# PCB_0009.net
KiCad netlist of a schematic drawn in EAGLE
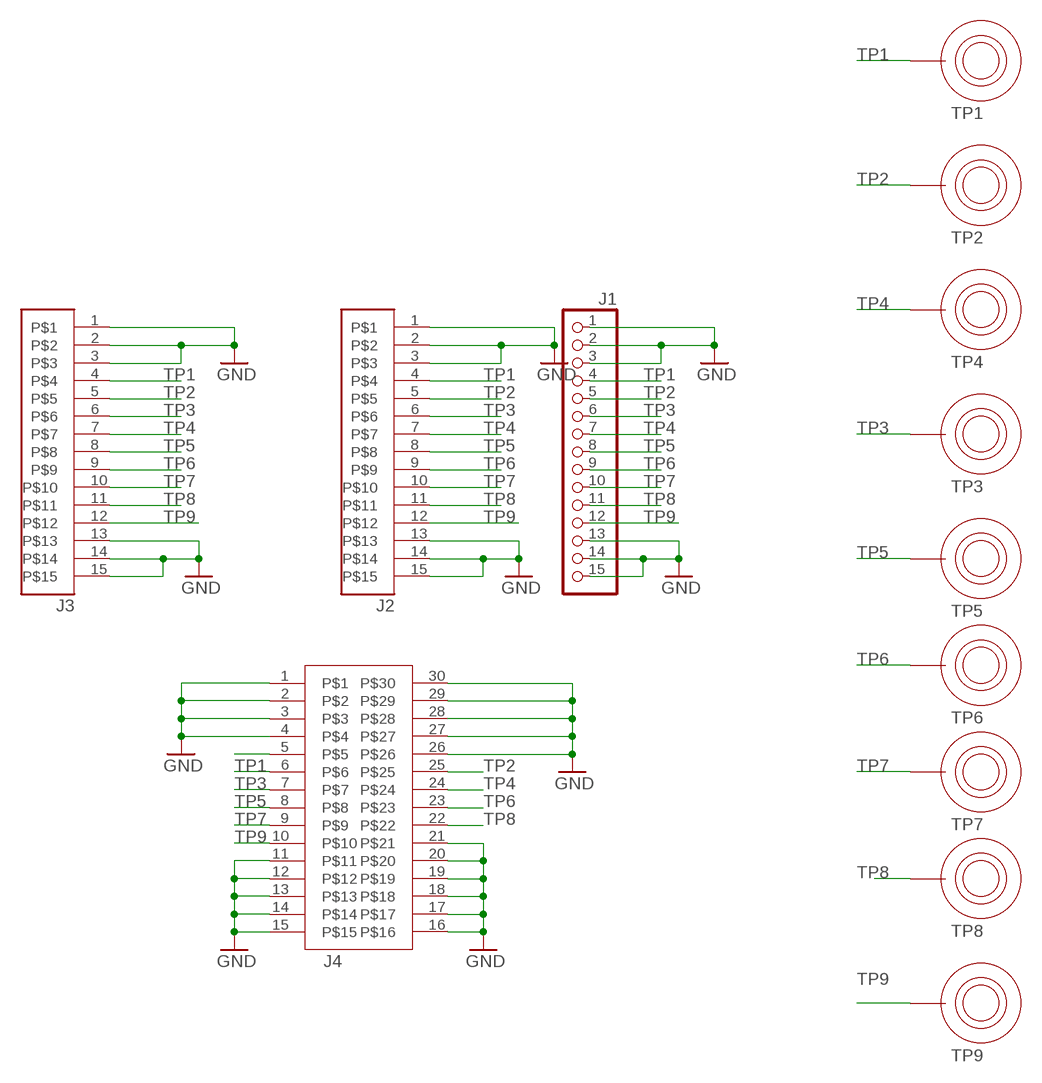
[diagram p0: schematic, sheet 1]

(export (version "E")
  (design (tool "Eeschema 10.0.6"))
  (components
    (comp (ref "J1")
      (value "PINHD-1X15")
      (footprint "eagle-import:1X15")
      (libsource (lib "eagle-import") (part "PINHD-1X15"))
    )
    (comp (ref "J2")
      (value "HEADER_15X1RA_SMT_HACK")
      (footprint "eagle-import:HEADER_1X15_RA_SMT_HACK")
      (libsource (lib "eagle-import") (part "HEADER_15X1RA_SMT_HACK"))
    )
    (comp (ref "J3")
      (value "HEADER_15X1SMT")
      (footprint "eagle-import:HDRV_SMD_15S736P254_1X15_3860X508X965")
      (libsource (lib "eagle-import") (part "HEADER_15X1SMT"))
    )
    (comp (ref "J4")
      (value "HEADER_15X2SMT")
      (footprint "eagle-import:HDRV_SMD_30S736P254_2X15_3860X508X965")
      (libsource (lib "eagle-import") (part "HEADER_15X2SMT"))
    )
    (comp (ref "TP1")
      (value "TOUCHPADROUND15MM")
      (footprint "eagle-import:TOUCHPAD_ROUND_15MM")
      (libsource (lib "eagle-import") (part "TOUCHPADROUND15MM"))
    )
    (comp (ref "TP2")
      (value "TOUCHPADROUND15MM")
      (footprint "eagle-import:TOUCHPAD_ROUND_15MM")
      (libsource (lib "eagle-import") (part "TOUCHPADROUND15MM"))
    )
    (comp (ref "TP3")
      (value "TOUCHPADROUND15MM")
      (footprint "eagle-import:TOUCHPAD_ROUND_15MM")
      (libsource (lib "eagle-import") (part "TOUCHPADROUND15MM"))
    )
    (comp (ref "TP4")
      (value "TOUCHPADROUND15MM")
      (footprint "eagle-import:TOUCHPAD_ROUND_15MM")
      (libsource (lib "eagle-import") (part "TOUCHPADROUND15MM"))
    )
    (comp (ref "TP5")
      (value "TOUCHPADROUND15MM")
      (footprint "eagle-import:TOUCHPAD_ROUND_15MM")
      (libsource (lib "eagle-import") (part "TOUCHPADROUND15MM"))
    )
    (comp (ref "TP6")
      (value "TOUCHPADROUND15MM")
      (footprint "eagle-import:TOUCHPAD_ROUND_15MM")
      (libsource (lib "eagle-import") (part "TOUCHPADROUND15MM"))
    )
    (comp (ref "TP7")
      (value "TOUCHPADROUND15MM")
      (footprint "eagle-import:TOUCHPAD_ROUND_15MM")
      (libsource (lib "eagle-import") (part "TOUCHPADROUND15MM"))
    )
    (comp (ref "TP8")
      (value "TOUCHPADROUND15MM")
      (footprint "eagle-import:TOUCHPAD_ROUND_15MM")
      (libsource (lib "eagle-import") (part "TOUCHPADROUND15MM"))
    )
    (comp (ref "TP9")
      (value "TOUCHPADROUND15MM")
      (footprint "eagle-import:TOUCHPAD_ROUND_15MM")
      (libsource (lib "eagle-import") (part "TOUCHPADROUND15MM"))
    )
  )
  (nets
    (net (code "1") (name "/TP1") (class "Default")
      (node (ref "J1") (pin "4") (pinfunction "4_4") (pintype "passive"))
      (node (ref "J2") (pin "4") (pinfunction "P$4_4") (pintype "bidirectional"))
      (node (ref "J3") (pin "4") (pinfunction "P$4_4") (pintype "bidirectional"))
      (node (ref "J4") (pin "6") (pinfunction "P$6_6") (pintype "bidirectional"))
      (node (ref "TP1") (pin "P$1") (pinfunction "P$1_P$1") (pintype "bidirectional"))
    )
    (net (code "2") (name "/TP2") (class "Default")
      (node (ref "J1") (pin "5") (pinfunction "5_5") (pintype "passive"))
      (node (ref "J2") (pin "5") (pinfunction "P$5_5") (pintype "bidirectional"))
      (node (ref "J3") (pin "5") (pinfunction "P$5_5") (pintype "bidirectional"))
      (node (ref "J4") (pin "25") (pinfunction "P$25_25") (pintype "bidirectional"))
      (node (ref "TP2") (pin "P$1") (pinfunction "P$1_P$1") (pintype "bidirectional"))
    )
    (net (code "3") (name "/TP3") (class "Default")
      (node (ref "J1") (pin "6") (pinfunction "6_6") (pintype "passive"))
      (node (ref "J2") (pin "6") (pinfunction "P$6_6") (pintype "bidirectional"))
      (node (ref "J3") (pin "6") (pinfunction "P$6_6") (pintype "bidirectional"))
      (node (ref "J4") (pin "7") (pinfunction "P$7_7") (pintype "bidirectional"))
      (node (ref "TP3") (pin "P$1") (pinfunction "P$1_P$1") (pintype "bidirectional"))
    )
    (net (code "4") (name "/TP4") (class "Default")
      (node (ref "J1") (pin "7") (pinfunction "7_7") (pintype "passive"))
      (node (ref "J2") (pin "7") (pinfunction "P$7_7") (pintype "bidirectional"))
      (node (ref "J3") (pin "7") (pinfunction "P$7_7") (pintype "bidirectional"))
      (node (ref "J4") (pin "24") (pinfunction "P$24_24") (pintype "bidirectional"))
      (node (ref "TP4") (pin "P$1") (pinfunction "P$1_P$1") (pintype "bidirectional"))
    )
    (net (code "5") (name "/TP5") (class "Default")
      (node (ref "J1") (pin "8") (pinfunction "8_8") (pintype "passive"))
      (node (ref "J2") (pin "8") (pinfunction "P$8_8") (pintype "bidirectional"))
      (node (ref "J3") (pin "8") (pinfunction "P$8_8") (pintype "bidirectional"))
      (node (ref "J4") (pin "8") (pinfunction "P$8_8") (pintype "bidirectional"))
      (node (ref "TP5") (pin "P$1") (pinfunction "P$1_P$1") (pintype "bidirectional"))
    )
    (net (code "6") (name "/TP6") (class "Default")
      (node (ref "J1") (pin "9") (pinfunction "9_9") (pintype "passive"))
      (node (ref "J2") (pin "9") (pinfunction "P$9_9") (pintype "bidirectional"))
      (node (ref "J3") (pin "9") (pinfunction "P$9_9") (pintype "bidirectional"))
      (node (ref "J4") (pin "23") (pinfunction "P$23_23") (pintype "bidirectional"))
      (node (ref "TP6") (pin "P$1") (pinfunction "P$1_P$1") (pintype "bidirectional"))
    )
    (net (code "7") (name "/TP7") (class "Default")
      (node (ref "J1") (pin "10") (pinfunction "10_10") (pintype "passive"))
      (node (ref "J2") (pin "10") (pinfunction "P$10_10") (pintype "bidirectional"))
      (node (ref "J3") (pin "10") (pinfunction "P$10_10") (pintype "bidirectional"))
      (node (ref "J4") (pin "9") (pinfunction "P$9_9") (pintype "bidirectional"))
      (node (ref "TP7") (pin "P$1") (pinfunction "P$1_P$1") (pintype "bidirectional"))
    )
    (net (code "8") (name "/TP8") (class "Default")
      (node (ref "J1") (pin "11") (pinfunction "11_11") (pintype "passive"))
      (node (ref "J2") (pin "11") (pinfunction "P$11_11") (pintype "bidirectional"))
      (node (ref "J3") (pin "11") (pinfunction "P$11_11") (pintype "bidirectional"))
      (node (ref "J4") (pin "22") (pinfunction "P$22_22") (pintype "bidirectional"))
      (node (ref "TP8") (pin "P$1") (pinfunction "P$1_P$1") (pintype "bidirectional"))
    )
    (net (code "9") (name "/TP9") (class "Default")
      (node (ref "J1") (pin "12") (pinfunction "12_12") (pintype "passive"))
      (node (ref "J2") (pin "12") (pinfunction "P$12_12") (pintype "bidirectional"))
      (node (ref "J3") (pin "12") (pinfunction "P$12_12") (pintype "bidirectional"))
      (node (ref "J4") (pin "10") (pinfunction "P$10_10") (pintype "bidirectional"))
      (node (ref "TP9") (pin "P$1") (pinfunction "P$1_P$1") (pintype "bidirectional"))
    )
    (net (code "10") (name "GND") (class "Default")
      (node (ref "J1") (pin "1") (pinfunction "1_1") (pintype "passive"))
      (node (ref "J1") (pin "13") (pinfunction "13_13") (pintype "passive"))
      (node (ref "J1") (pin "14") (pinfunction "14_14") (pintype "passive"))
      (node (ref "J1") (pin "15") (pinfunction "15_15") (pintype "passive"))
      (node (ref "J1") (pin "2") (pinfunction "2_2") (pintype "passive"))
      (node (ref "J1") (pin "3") (pinfunction "3_3") (pintype "passive"))
      (node (ref "J2") (pin "1") (pinfunction "P$1_1") (pintype "bidirectional"))
      (node (ref "J2") (pin "13") (pinfunction "P$13_13") (pintype "bidirectional"))
      (node (ref "J2") (pin "14") (pinfunction "P$14_14") (pintype "bidirectional"))
      (node (ref "J2") (pin "15") (pinfunction "P$15_15") (pintype "bidirectional"))
      (node (ref "J2") (pin "2") (pinfunction "P$2_2") (pintype "bidirectional"))
      (node (ref "J2") (pin "3") (pinfunction "P$3_3") (pintype "bidirectional"))
      (node (ref "J3") (pin "1") (pinfunction "P$1_1") (pintype "bidirectional"))
      (node (ref "J3") (pin "13") (pinfunction "P$13_13") (pintype "bidirectional"))
      (node (ref "J3") (pin "14") (pinfunction "P$14_14") (pintype "bidirectional"))
      (node (ref "J3") (pin "15") (pinfunction "P$15_15") (pintype "bidirectional"))
      (node (ref "J3") (pin "2") (pinfunction "P$2_2") (pintype "bidirectional"))
      (node (ref "J3") (pin "3") (pinfunction "P$3_3") (pintype "bidirectional"))
      (node (ref "J4") (pin "1") (pinfunction "P$1_1") (pintype "bidirectional"))
      (node (ref "J4") (pin "11") (pinfunction "P$11_11") (pintype "bidirectional"))
      (node (ref "J4") (pin "12") (pinfunction "P$12_12") (pintype "bidirectional"))
      (node (ref "J4") (pin "13") (pinfunction "P$13_13") (pintype "bidirectional"))
      (node (ref "J4") (pin "14") (pinfunction "P$14_14") (pintype "bidirectional"))
      (node (ref "J4") (pin "15") (pinfunction "P$15_15") (pintype "bidirectional"))
      (node (ref "J4") (pin "16") (pinfunction "P$16_16") (pintype "bidirectional"))
      (node (ref "J4") (pin "17") (pinfunction "P$17_17") (pintype "bidirectional"))
      (node (ref "J4") (pin "18") (pinfunction "P$18_18") (pintype "bidirectional"))
      (node (ref "J4") (pin "19") (pinfunction "P$19_19") (pintype "bidirectional"))
      (node (ref "J4") (pin "2") (pinfunction "P$2_2") (pintype "bidirectional"))
      (node (ref "J4") (pin "20") (pinfunction "P$20_20") (pintype "bidirectional"))
      (node (ref "J4") (pin "21") (pinfunction "P$21_21") (pintype "bidirectional"))
      (node (ref "J4") (pin "26") (pinfunction "P$26_26") (pintype "bidirectional"))
      (node (ref "J4") (pin "27") (pinfunction "P$27_27") (pintype "bidirectional"))
      (node (ref "J4") (pin "28") (pinfunction "P$28_28") (pintype "bidirectional"))
      (node (ref "J4") (pin "29") (pinfunction "P$29_29") (pintype "bidirectional"))
      (node (ref "J4") (pin "3") (pinfunction "P$3_3") (pintype "bidirectional"))
      (node (ref "J4") (pin "30") (pinfunction "P$30_30") (pintype "bidirectional"))
      (node (ref "J4") (pin "4") (pinfunction "P$4_4") (pintype "bidirectional"))
    )
    (net (code "11") (name "unconnected-(J4-P$5-Pad5)") (class "Default")
      (node (ref "J4") (pin "5") (pinfunction "P$5_5") (pintype "bidirectional"))
    )
  )
)
